# acDetector.net
KiCad netlist of a schematic drawn in Altium Designer
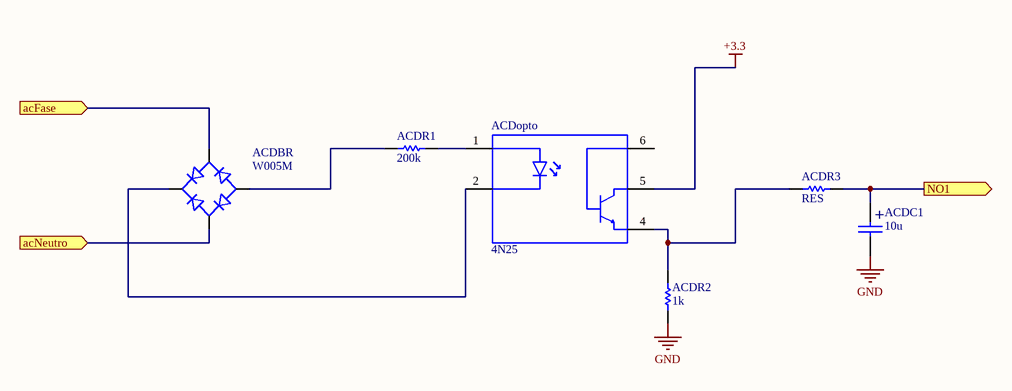
[diagram p0: acDetector.SchDoc]

(export (version "E")
  (design (tool "Eeschema 10.0.6"))
  (components
    (comp (ref "ACDBR")
      (value "W005M")
      (footprint "DIOB_W005M")
      (description "Bridge Rectifier Single Phase Standard 50V Through Hole WOM")
      (fields (field (name "MF") "GeneSiC Semiconductor"))
      (libsource (lib "W005M") (part "W005M"))
    )
    (comp (ref "ACDC1") (value "10u") (footprint "CAP100RP") (libsource (lib "LIBEBAL") (part "CAPPOL")))
    (comp (ref "ACDopto")
      (value "4N25")
      (footprint "LIBEBAL:DIP6")
      (description "Optoisolator Transistor with Base Output 5000Vrms 1 Channel 6-DIP")
      (fields (field (name "MF") "Vishay Semiconductor"))
      (libsource (lib "4N25") (part "4N25"))
    )
    (comp (ref "ACDR1") (value "200k") (footprint "RES400") (libsource (lib "LIBEBAL") (part "RES")))
    (comp (ref "ACDR2") (value "1k") (footprint "RES400") (libsource (lib "LIBEBAL") (part "RES")))
    (comp (ref "ACDR3") (value "RES") (footprint "RES400") (libsource (lib "LIBEBAL") (part "RES")))
  )
  (nets
    (net (code "1") (name "+3.3") (class "Default")
      (node (ref "ACDopto") (pin "5") (pinfunction "C_5") (pintype "passive"))
    )
    (net (code "2") (name "/NO1") (class "Default")
      (node (ref "ACDC1") (pin "1") (pinfunction "1_1") (pintype "passive"))
      (node (ref "ACDR3") (pin "2") (pinfunction "2_2") (pintype "passive"))
    )
    (net (code "3") (name "/acFase") (class "Default")
      (node (ref "ACDBR") (pin "2") (pinfunction "AC1_2") (pintype "passive"))
    )
    (net (code "4") (name "/acNeutro") (class "Default")
      (node (ref "ACDBR") (pin "4") (pinfunction "AC2_4") (pintype "passive"))
    )
    (net (code "5") (name "GND") (class "Default")
      (node (ref "ACDC1") (pin "2") (pinfunction "2_2") (pintype "passive"))
      (node (ref "ACDR2") (pin "1") (pinfunction "1_1") (pintype "passive"))
    )
    (net (code "6") (name "Net-(ACDBR-NEG)") (class "Default")
      (node (ref "ACDBR") (pin "3") (pinfunction "NEG_3") (pintype "passive"))
      (node (ref "ACDR1") (pin "1") (pinfunction "1_1") (pintype "passive"))
    )
    (net (code "7") (name "Net-(ACDBR-POS)") (class "Default")
      (node (ref "ACDBR") (pin "1") (pinfunction "POS_1") (pintype "passive"))
      (node (ref "ACDopto") (pin "2") (pinfunction "K_2") (pintype "passive"))
    )
    (net (code "8") (name "Net-(ACDopto-A)") (class "Default")
      (node (ref "ACDR1") (pin "2") (pinfunction "2_2") (pintype "passive"))
      (node (ref "ACDopto") (pin "1") (pinfunction "A_1") (pintype "passive"))
    )
    (net (code "9") (name "Net-(ACDopto-E)") (class "Default")
      (node (ref "ACDR2") (pin "2") (pinfunction "2_2") (pintype "passive"))
      (node (ref "ACDR3") (pin "1") (pinfunction "1_1") (pintype "passive"))
      (node (ref "ACDopto") (pin "4") (pinfunction "E_4") (pintype "passive"))
    )
    (net (code "10") (name "unconnected-(ACDopto-B-Pad6)") (class "Default")
      (node (ref "ACDopto") (pin "6") (pinfunction "B_6") (pintype "passive"))
    )
  )
)
